# edition4-mainpart-3.net
KiCad netlist of a schematic drawn in EAGLE
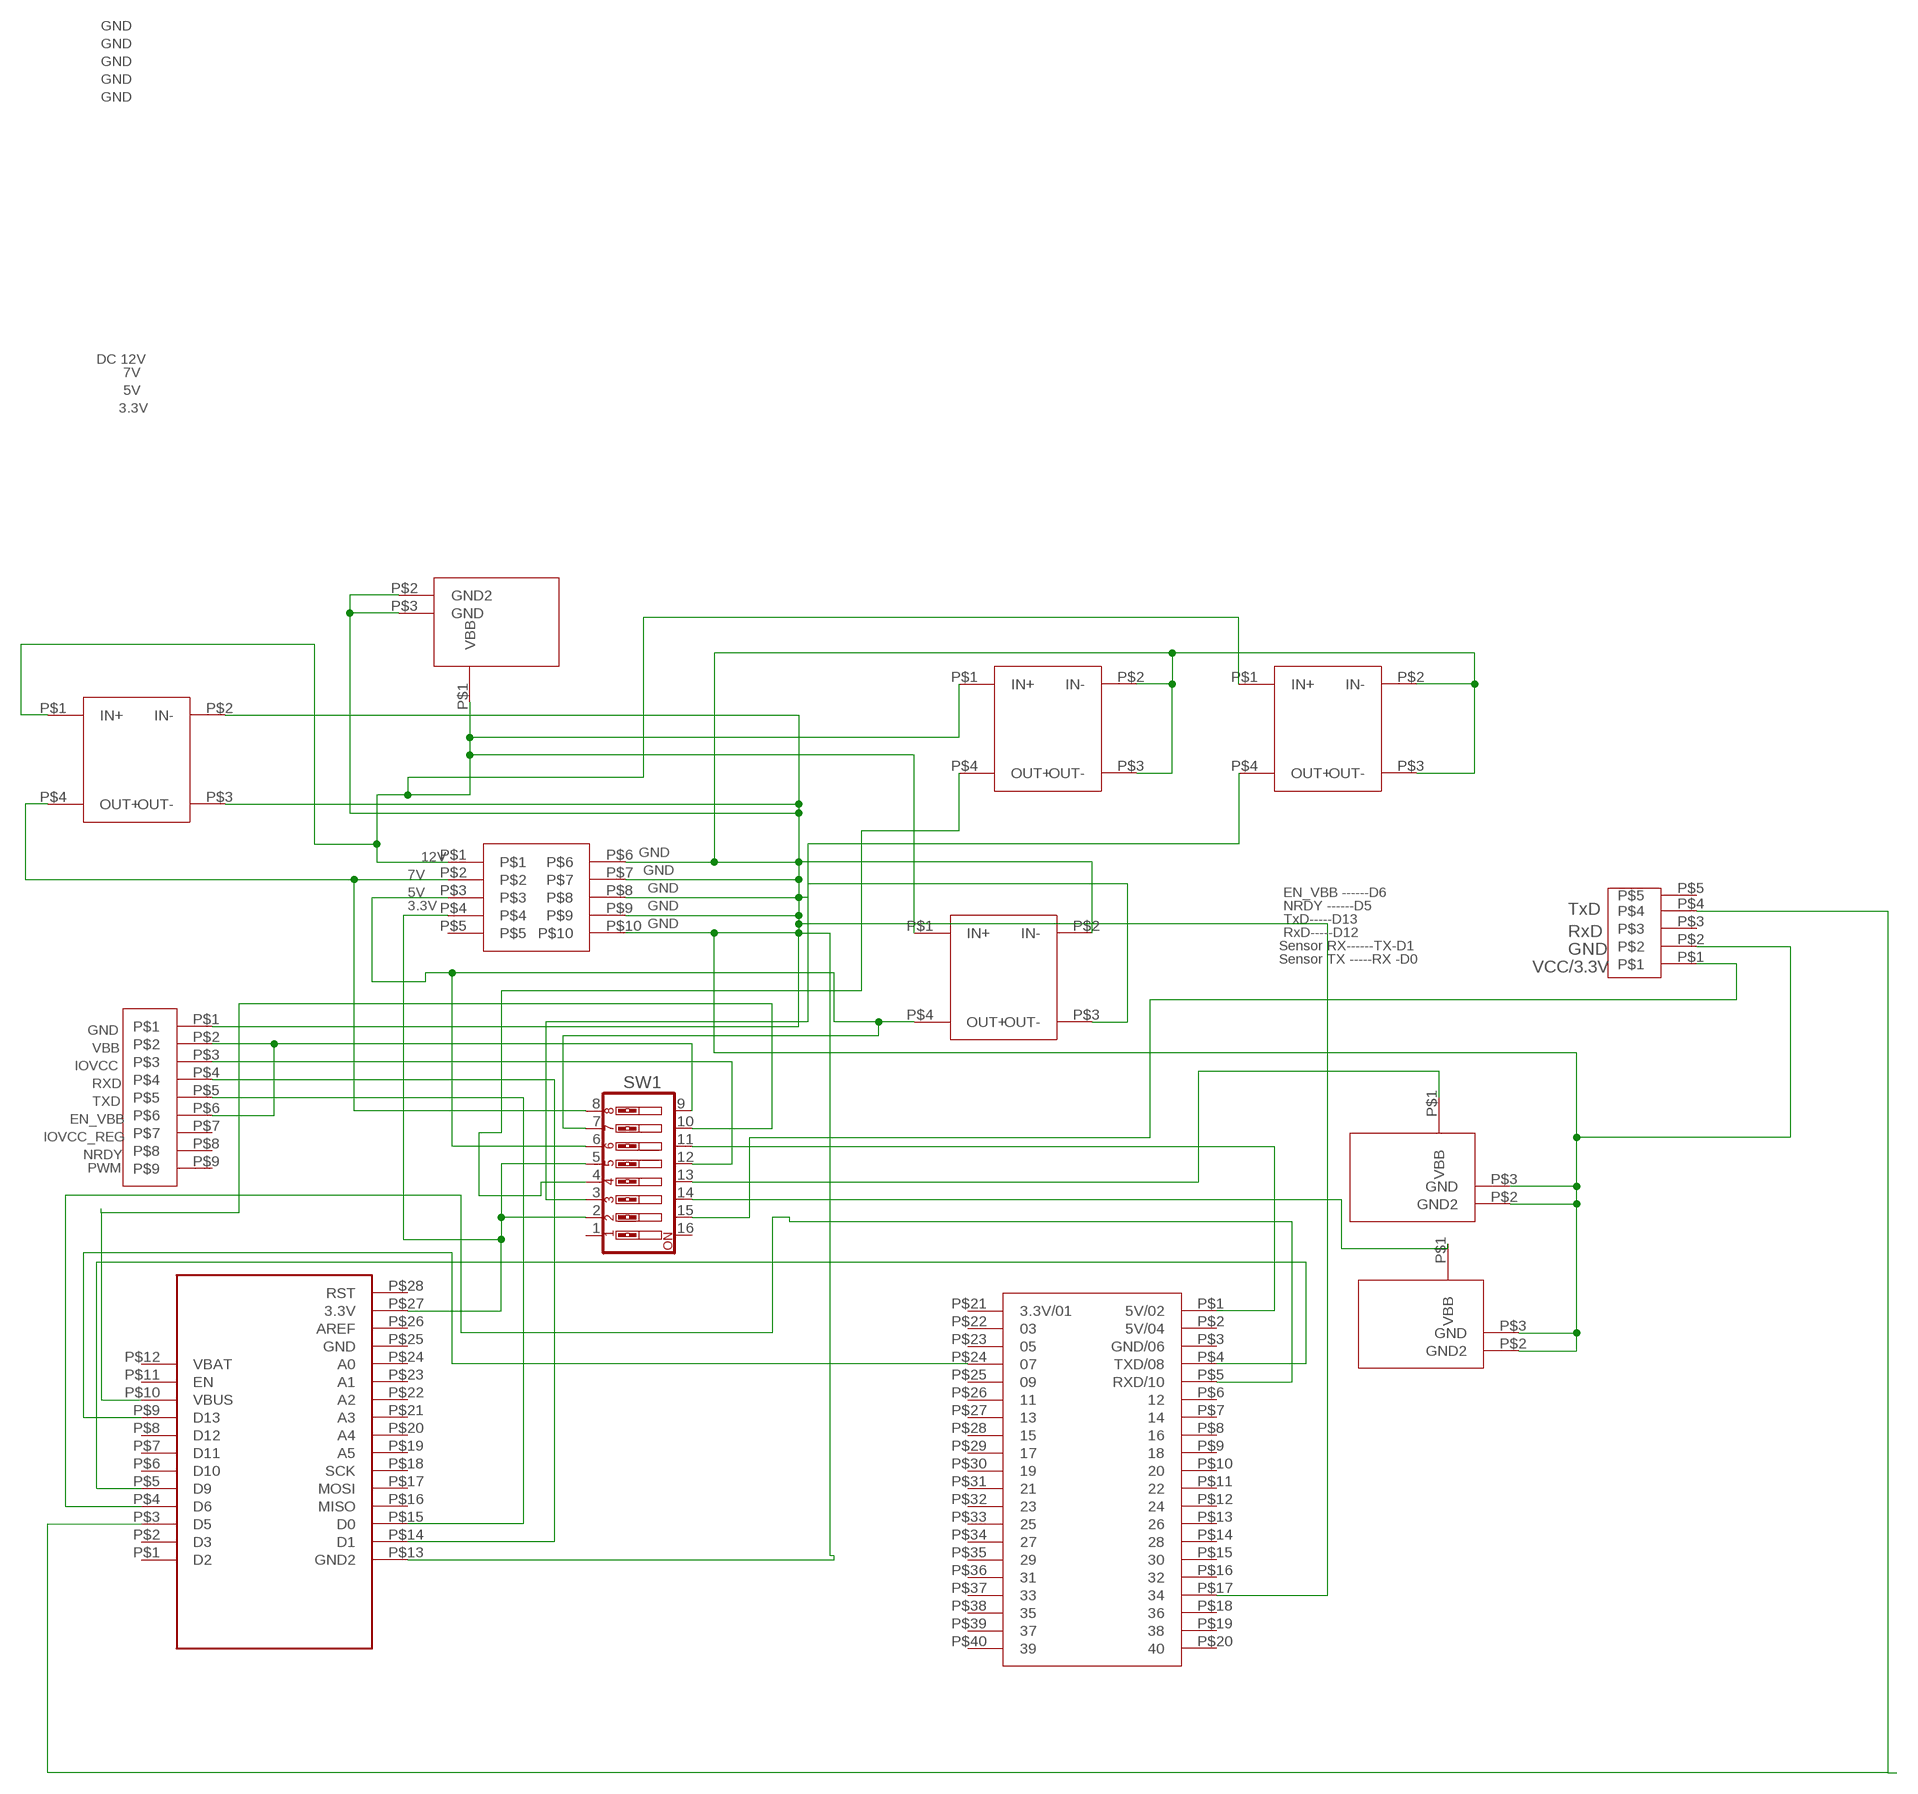
[diagram p0: schematic, sheet 1]

(export (version "E")
  (design (tool "Eeschema 10.0.6"))
  (components
    (comp (ref "SW1")
      (value "SW_DIP-8")
      (footprint "eagle-import:EDG-08")
      (libsource (lib "eagle-import") (part "SW_DIP-8"))
    )
    (comp (ref "U$1")
      (value "MH-MINI-360")
      (footprint "eagle-import:MH-MINI-360")
      (libsource (lib "eagle-import") (part "MH-MINI-360"))
    )
    (comp (ref "U$2")
      (value "MH-MINI-360")
      (footprint "eagle-import:MH-MINI-360")
      (libsource (lib "eagle-import") (part "MH-MINI-360"))
    )
    (comp (ref "U$3")
      (value "POWER")
      (footprint "eagle-import:POWERIN")
      (libsource (lib "eagle-import") (part "POWER"))
    )
    (comp (ref "U$4")
      (value "POWER")
      (footprint "eagle-import:POWERIN")
      (libsource (lib "eagle-import") (part "POWER"))
    )
    (comp (ref "U$5")
      (value "POWER")
      (footprint "eagle-import:POWERIN")
      (libsource (lib "eagle-import") (part "POWER"))
    )
    (comp (ref "U$6")
      (value "MH-MINI-360")
      (footprint "eagle-import:MH-MINI-360")
      (libsource (lib "eagle-import") (part "MH-MINI-360"))
    )
    (comp (ref "U$7")
      (value "MH-MINI-360")
      (footprint "eagle-import:MH-MINI-360")
      (libsource (lib "eagle-import") (part "MH-MINI-360"))
    )
    (comp (ref "U$8")
      (value "PIN")
      (footprint "eagle-import:PIN")
      (libsource (lib "eagle-import") (part "PIN"))
    )
    (comp (ref "U$10")
      (value "FEATHER")
      (footprint "eagle-import:FEATHER")
      (libsource (lib "eagle-import") (part "FEATHER"))
    )
    (comp (ref "U$11")
      (value "RASPBERRYPI")
      (footprint "eagle-import:RASPBERRYPI")
      (libsource (lib "eagle-import") (part "RASPBERRYPI"))
    )
    (comp (ref "U$14")
      (value "2X5FEET")
      (footprint "eagle-import:2X5FEET")
      (libsource (lib "eagle-import") (part "2X5FEET"))
    )
    (comp (ref "U$15")
      (value "9FEETPIN")
      (footprint "eagle-import:9FEETPIN")
      (libsource (lib "eagle-import") (part "9FEETPIN"))
    )
  )
  (nets
    (net (code "1") (name "Net-(SW1-Pad9)") (class "Default")
      (node (ref "SW1") (pin "9") (pinfunction "9_9") (pintype "passive"))
      (node (ref "U$15") (pin "P$2") (pinfunction "P$2_P$2") (pintype "bidirectional"))
      (node (ref "U$15") (pin "P$6") (pinfunction "P$6_P$6") (pintype "bidirectional"))
    )
    (net (code "2") (name "Net-(SW1-Pad12)") (class "Default")
      (node (ref "SW1") (pin "12") (pinfunction "12_12") (pintype "passive"))
      (node (ref "U$15") (pin "P$3") (pinfunction "P$3_P$3") (pintype "bidirectional"))
    )
    (net (code "3") (name "Net-(SW1-Pad15)") (class "Default")
      (node (ref "SW1") (pin "15") (pinfunction "15_15") (pintype "passive"))
      (node (ref "U$8") (pin "P$1") (pinfunction "P$1_P$1") (pintype "bidirectional"))
    )
    (net (code "4") (name "Net-(U$1-IN+)") (class "Default")
      (node (ref "U$1") (pin "P$1") (pinfunction "IN+_P$1") (pintype "bidirectional"))
      (node (ref "U$14") (pin "P$1") (pinfunction "P$1_P$1") (pintype "bidirectional"))
      (node (ref "U$2") (pin "P$1") (pinfunction "IN+_P$1") (pintype "bidirectional"))
      (node (ref "U$3") (pin "P$1") (pinfunction "VBB_P$1") (pintype "bidirectional"))
      (node (ref "U$6") (pin "P$1") (pinfunction "IN+_P$1") (pintype "bidirectional"))
      (node (ref "U$7") (pin "P$1") (pinfunction "IN+_P$1") (pintype "bidirectional"))
    )
    (net (code "5") (name "Net-(U$1-IN-)") (class "Default")
      (node (ref "U$1") (pin "P$2") (pinfunction "IN-_P$2") (pintype "bidirectional"))
      (node (ref "U$1") (pin "P$3") (pinfunction "OUT-_P$3") (pintype "bidirectional"))
      (node (ref "U$10") (pin "P$13") (pinfunction "GND2_P$13") (pintype "bidirectional"))
      (node (ref "U$11") (pin "P$17") (pinfunction "34_P$17") (pintype "bidirectional"))
      (node (ref "U$14") (pin "P$10") (pinfunction "P$10_P$10") (pintype "bidirectional"))
      (node (ref "U$14") (pin "P$6") (pinfunction "P$6_P$6") (pintype "bidirectional"))
      (node (ref "U$14") (pin "P$7") (pinfunction "P$7_P$7") (pintype "bidirectional"))
      (node (ref "U$14") (pin "P$8") (pinfunction "P$8_P$8") (pintype "bidirectional"))
      (node (ref "U$14") (pin "P$9") (pinfunction "P$9_P$9") (pintype "bidirectional"))
      (node (ref "U$15") (pin "P$1") (pinfunction "P$1_P$1") (pintype "bidirectional"))
      (node (ref "U$2") (pin "P$2") (pinfunction "IN-_P$2") (pintype "bidirectional"))
      (node (ref "U$2") (pin "P$3") (pinfunction "OUT-_P$3") (pintype "bidirectional"))
      (node (ref "U$3") (pin "P$2") (pinfunction "GND2_P$2") (pintype "bidirectional"))
      (node (ref "U$3") (pin "P$3") (pinfunction "GND_P$3") (pintype "bidirectional"))
      (node (ref "U$4") (pin "P$2") (pinfunction "GND2_P$2") (pintype "bidirectional"))
      (node (ref "U$4") (pin "P$3") (pinfunction "GND_P$3") (pintype "bidirectional"))
      (node (ref "U$5") (pin "P$2") (pinfunction "GND2_P$2") (pintype "bidirectional"))
      (node (ref "U$5") (pin "P$3") (pinfunction "GND_P$3") (pintype "bidirectional"))
      (node (ref "U$6") (pin "P$2") (pinfunction "IN-_P$2") (pintype "bidirectional"))
      (node (ref "U$6") (pin "P$3") (pinfunction "OUT-_P$3") (pintype "bidirectional"))
      (node (ref "U$7") (pin "P$2") (pinfunction "IN-_P$2") (pintype "bidirectional"))
      (node (ref "U$7") (pin "P$3") (pinfunction "OUT-_P$3") (pintype "bidirectional"))
      (node (ref "U$8") (pin "P$2") (pinfunction "P$2_P$2") (pintype "bidirectional"))
    )
    (net (code "6") (name "Net-(U$1-OUT+)") (class "Default")
      (node (ref "SW1") (pin "4") (pinfunction "4_4") (pintype "passive"))
      (node (ref "U$1") (pin "P$4") (pinfunction "OUT+_P$4") (pintype "bidirectional"))
    )
    (net (code "7") (name "Net-(U$2-OUT+)") (class "Default")
      (node (ref "SW1") (pin "6") (pinfunction "6_6") (pintype "passive"))
      (node (ref "SW1") (pin "7") (pinfunction "7_7") (pintype "passive"))
      (node (ref "U$14") (pin "P$3") (pinfunction "P$3_P$3") (pintype "bidirectional"))
      (node (ref "U$2") (pin "P$4") (pinfunction "OUT+_P$4") (pintype "bidirectional"))
    )
    (net (code "8") (name "Net-(U$4-VBB)") (class "Default")
      (node (ref "SW1") (pin "14") (pinfunction "14_14") (pintype "passive"))
      (node (ref "U$4") (pin "P$1") (pinfunction "VBB_P$1") (pintype "bidirectional"))
    )
    (net (code "9") (name "Net-(U$5-VBB)") (class "Default")
      (node (ref "SW1") (pin "13") (pinfunction "13_13") (pintype "passive"))
      (node (ref "U$5") (pin "P$1") (pinfunction "VBB_P$1") (pintype "bidirectional"))
    )
    (net (code "10") (name "Net-(U$6-OUT+)") (class "Default")
      (node (ref "SW1") (pin "8") (pinfunction "8_8") (pintype "passive"))
      (node (ref "U$14") (pin "P$2") (pinfunction "P$2_P$2") (pintype "bidirectional"))
      (node (ref "U$6") (pin "P$4") (pinfunction "OUT+_P$4") (pintype "bidirectional"))
    )
    (net (code "11") (name "Net-(U$7-OUT+)") (class "Default")
      (node (ref "SW1") (pin "3") (pinfunction "3_3") (pintype "passive"))
      (node (ref "U$7") (pin "P$4") (pinfunction "OUT+_P$4") (pintype "bidirectional"))
    )
    (net (code "12") (name "Net-(U$10-3.3V)") (class "Default")
      (node (ref "SW1") (pin "2") (pinfunction "2_2") (pintype "passive"))
      (node (ref "SW1") (pin "5") (pinfunction "5_5") (pintype "passive"))
      (node (ref "U$10") (pin "P$27") (pinfunction "3.3V_P$27") (pintype "bidirectional"))
      (node (ref "U$14") (pin "P$4") (pinfunction "P$4_P$4") (pintype "bidirectional"))
    )
    (net (code "13") (name "Net-(U$10-D0)") (class "Default")
      (node (ref "U$10") (pin "P$15") (pinfunction "D0_P$15") (pintype "bidirectional"))
      (node (ref "U$15") (pin "P$5") (pinfunction "P$5_P$5") (pintype "bidirectional"))
    )
    (net (code "14") (name "Net-(U$10-D1)") (class "Default")
      (node (ref "U$10") (pin "P$14") (pinfunction "D1_P$14") (pintype "bidirectional"))
      (node (ref "U$15") (pin "P$4") (pinfunction "P$4_P$4") (pintype "bidirectional"))
    )
    (net (code "15") (name "Net-(U$10-D5)") (class "Default")
      (node (ref "U$10") (pin "P$3") (pinfunction "D5_P$3") (pintype "bidirectional"))
      (node (ref "U$8") (pin "P$4") (pinfunction "P$4_P$4") (pintype "bidirectional"))
    )
    (net (code "16") (name "Net-(U$10-D6)") (class "Default")
      (node (ref "U$10") (pin "P$4") (pinfunction "D6_P$4") (pintype "bidirectional"))
      (node (ref "U$11") (pin "P$5") (pinfunction "RXD/10_P$5") (pintype "bidirectional"))
    )
    (net (code "17") (name "Net-(U$10-D9)") (class "Default")
      (node (ref "U$10") (pin "P$5") (pinfunction "D9_P$5") (pintype "bidirectional"))
      (node (ref "U$11") (pin "P$4") (pinfunction "TXD/08_P$4") (pintype "bidirectional"))
    )
    (net (code "18") (name "Net-(U$10-D13)") (class "Default")
      (node (ref "U$10") (pin "P$9") (pinfunction "D13_P$9") (pintype "bidirectional"))
      (node (ref "U$11") (pin "P$24") (pinfunction "07_P$24") (pintype "bidirectional"))
    )
    (net (code "19") (name "Net-(U$10-VBUS)") (class "Default")
      (node (ref "SW1") (pin "10") (pinfunction "10_10") (pintype "passive"))
      (node (ref "U$10") (pin "P$10") (pinfunction "VBUS_P$10") (pintype "bidirectional"))
    )
    (net (code "20") (name "Net-(U$11-5V{slash}02)") (class "Default")
      (node (ref "SW1") (pin "11") (pinfunction "11_11") (pintype "passive"))
      (node (ref "U$11") (pin "P$1") (pinfunction "5V/02_P$1") (pintype "bidirectional"))
    )
    (net (code "21") (name "unconnected-(SW1-Pad1)") (class "Default")
      (node (ref "SW1") (pin "1") (pinfunction "1_1") (pintype "passive"))
    )
    (net (code "22") (name "unconnected-(SW1-Pad16)") (class "Default")
      (node (ref "SW1") (pin "16") (pinfunction "16_16") (pintype "passive"))
    )
    (net (code "23") (name "unconnected-(U$8-PadP$3)") (class "Default")
      (node (ref "U$8") (pin "P$3") (pinfunction "P$3_P$3") (pintype "bidirectional"))
    )
    (net (code "24") (name "unconnected-(U$8-PadP$5)") (class "Default")
      (node (ref "U$8") (pin "P$5") (pinfunction "P$5_P$5") (pintype "bidirectional"))
    )
    (net (code "25") (name "unconnected-(U$10-A0-PadP$24)") (class "Default")
      (node (ref "U$10") (pin "P$24") (pinfunction "A0_P$24") (pintype "bidirectional"))
    )
    (net (code "26") (name "unconnected-(U$10-A1-PadP$23)") (class "Default")
      (node (ref "U$10") (pin "P$23") (pinfunction "A1_P$23") (pintype "bidirectional"))
    )
    (net (code "27") (name "unconnected-(U$10-A2-PadP$22)") (class "Default")
      (node (ref "U$10") (pin "P$22") (pinfunction "A2_P$22") (pintype "bidirectional"))
    )
    (net (code "28") (name "unconnected-(U$10-A3-PadP$21)") (class "Default")
      (node (ref "U$10") (pin "P$21") (pinfunction "A3_P$21") (pintype "bidirectional"))
    )
    (net (code "29") (name "unconnected-(U$10-A4-PadP$20)") (class "Default")
      (node (ref "U$10") (pin "P$20") (pinfunction "A4_P$20") (pintype "bidirectional"))
    )
    (net (code "30") (name "unconnected-(U$10-A5-PadP$19)") (class "Default")
      (node (ref "U$10") (pin "P$19") (pinfunction "A5_P$19") (pintype "bidirectional"))
    )
    (net (code "31") (name "unconnected-(U$10-AREF-PadP$26)") (class "Default")
      (node (ref "U$10") (pin "P$26") (pinfunction "AREF_P$26") (pintype "bidirectional"))
    )
    (net (code "32") (name "unconnected-(U$10-D2-PadP$1)") (class "Default")
      (node (ref "U$10") (pin "P$1") (pinfunction "D2_P$1") (pintype "bidirectional"))
    )
    (net (code "33") (name "unconnected-(U$10-D3-PadP$2)") (class "Default")
      (node (ref "U$10") (pin "P$2") (pinfunction "D3_P$2") (pintype "bidirectional"))
    )
    (net (code "34") (name "unconnected-(U$10-D10-PadP$6)") (class "Default")
      (node (ref "U$10") (pin "P$6") (pinfunction "D10_P$6") (pintype "bidirectional"))
    )
    (net (code "35") (name "unconnected-(U$10-D11-PadP$7)") (class "Default")
      (node (ref "U$10") (pin "P$7") (pinfunction "D11_P$7") (pintype "bidirectional"))
    )
    (net (code "36") (name "unconnected-(U$10-D12-PadP$8)") (class "Default")
      (node (ref "U$10") (pin "P$8") (pinfunction "D12_P$8") (pintype "bidirectional"))
    )
    (net (code "37") (name "unconnected-(U$10-EN-PadP$11)") (class "Default")
      (node (ref "U$10") (pin "P$11") (pinfunction "EN_P$11") (pintype "bidirectional"))
    )
    (net (code "38") (name "unconnected-(U$10-GND-PadP$25)") (class "Default")
      (node (ref "U$10") (pin "P$25") (pinfunction "GND_P$25") (pintype "bidirectional"))
    )
    (net (code "39") (name "unconnected-(U$10-MISO-PadP$16)") (class "Default")
      (node (ref "U$10") (pin "P$16") (pinfunction "MISO_P$16") (pintype "bidirectional"))
    )
    (net (code "40") (name "unconnected-(U$10-MOSI-PadP$17)") (class "Default")
      (node (ref "U$10") (pin "P$17") (pinfunction "MOSI_P$17") (pintype "bidirectional"))
    )
    (net (code "41") (name "unconnected-(U$10-RST-PadP$28)") (class "Default")
      (node (ref "U$10") (pin "P$28") (pinfunction "RST_P$28") (pintype "bidirectional"))
    )
    (net (code "42") (name "unconnected-(U$10-SCK-PadP$18)") (class "Default")
      (node (ref "U$10") (pin "P$18") (pinfunction "SCK_P$18") (pintype "bidirectional"))
    )
    (net (code "43") (name "unconnected-(U$10-VBAT-PadP$12)") (class "Default")
      (node (ref "U$10") (pin "P$12") (pinfunction "VBAT_P$12") (pintype "bidirectional"))
    )
    (net (code "44") (name "unconnected-(U$11-03-PadP$22)") (class "Default")
      (node (ref "U$11") (pin "P$22") (pinfunction "03_P$22") (pintype "bidirectional"))
    )
    (net (code "45") (name "unconnected-(U$11-3.3V{slash}01-PadP$21)") (class "Default")
      (node (ref "U$11") (pin "P$21") (pinfunction "3.3V/01_P$21") (pintype "bidirectional"))
    )
    (net (code "46") (name "unconnected-(U$11-05-PadP$23)") (class "Default")
      (node (ref "U$11") (pin "P$23") (pinfunction "05_P$23") (pintype "bidirectional"))
    )
    (net (code "47") (name "unconnected-(U$11-5V{slash}04-PadP$2)") (class "Default")
      (node (ref "U$11") (pin "P$2") (pinfunction "5V/04_P$2") (pintype "bidirectional"))
    )
    (net (code "48") (name "unconnected-(U$11-09-PadP$25)") (class "Default")
      (node (ref "U$11") (pin "P$25") (pinfunction "09_P$25") (pintype "bidirectional"))
    )
    (net (code "49") (name "unconnected-(U$11-11-PadP$26)") (class "Default")
      (node (ref "U$11") (pin "P$26") (pinfunction "11_P$26") (pintype "bidirectional"))
    )
    (net (code "50") (name "unconnected-(U$11-12-PadP$6)") (class "Default")
      (node (ref "U$11") (pin "P$6") (pinfunction "12_P$6") (pintype "bidirectional"))
    )
    (net (code "51") (name "unconnected-(U$11-13-PadP$27)") (class "Default")
      (node (ref "U$11") (pin "P$27") (pinfunction "13_P$27") (pintype "bidirectional"))
    )
    (net (code "52") (name "unconnected-(U$11-14-PadP$7)") (class "Default")
      (node (ref "U$11") (pin "P$7") (pinfunction "14_P$7") (pintype "bidirectional"))
    )
    (net (code "53") (name "unconnected-(U$11-15-PadP$28)") (class "Default")
      (node (ref "U$11") (pin "P$28") (pinfunction "15_P$28") (pintype "bidirectional"))
    )
    (net (code "54") (name "unconnected-(U$11-16-PadP$8)") (class "Default")
      (node (ref "U$11") (pin "P$8") (pinfunction "16_P$8") (pintype "bidirectional"))
    )
    (net (code "55") (name "unconnected-(U$11-17-PadP$29)") (class "Default")
      (node (ref "U$11") (pin "P$29") (pinfunction "17_P$29") (pintype "bidirectional"))
    )
    (net (code "56") (name "unconnected-(U$11-18-PadP$9)") (class "Default")
      (node (ref "U$11") (pin "P$9") (pinfunction "18_P$9") (pintype "bidirectional"))
    )
    (net (code "57") (name "unconnected-(U$11-19-PadP$30)") (class "Default")
      (node (ref "U$11") (pin "P$30") (pinfunction "19_P$30") (pintype "bidirectional"))
    )
    (net (code "58") (name "unconnected-(U$11-20-PadP$10)") (class "Default")
      (node (ref "U$11") (pin "P$10") (pinfunction "20_P$10") (pintype "bidirectional"))
    )
    (net (code "59") (name "unconnected-(U$11-21-PadP$31)") (class "Default")
      (node (ref "U$11") (pin "P$31") (pinfunction "21_P$31") (pintype "bidirectional"))
    )
    (net (code "60") (name "unconnected-(U$11-22-PadP$11)") (class "Default")
      (node (ref "U$11") (pin "P$11") (pinfunction "22_P$11") (pintype "bidirectional"))
    )
    (net (code "61") (name "unconnected-(U$11-23-PadP$32)") (class "Default")
      (node (ref "U$11") (pin "P$32") (pinfunction "23_P$32") (pintype "bidirectional"))
    )
    (net (code "62") (name "unconnected-(U$11-24-PadP$12)") (class "Default")
      (node (ref "U$11") (pin "P$12") (pinfunction "24_P$12") (pintype "bidirectional"))
    )
    (net (code "63") (name "unconnected-(U$11-25-PadP$33)") (class "Default")
      (node (ref "U$11") (pin "P$33") (pinfunction "25_P$33") (pintype "bidirectional"))
    )
    (net (code "64") (name "unconnected-(U$11-26-PadP$13)") (class "Default")
      (node (ref "U$11") (pin "P$13") (pinfunction "26_P$13") (pintype "bidirectional"))
    )
    (net (code "65") (name "unconnected-(U$11-27-PadP$34)") (class "Default")
      (node (ref "U$11") (pin "P$34") (pinfunction "27_P$34") (pintype "bidirectional"))
    )
    (net (code "66") (name "unconnected-(U$11-28-PadP$14)") (class "Default")
      (node (ref "U$11") (pin "P$14") (pinfunction "28_P$14") (pintype "bidirectional"))
    )
    (net (code "67") (name "unconnected-(U$11-29-PadP$35)") (class "Default")
      (node (ref "U$11") (pin "P$35") (pinfunction "29_P$35") (pintype "bidirectional"))
    )
    (net (code "68") (name "unconnected-(U$11-30-PadP$15)") (class "Default")
      (node (ref "U$11") (pin "P$15") (pinfunction "30_P$15") (pintype "bidirectional"))
    )
    (net (code "69") (name "unconnected-(U$11-31-PadP$36)") (class "Default")
      (node (ref "U$11") (pin "P$36") (pinfunction "31_P$36") (pintype "bidirectional"))
    )
    (net (code "70") (name "unconnected-(U$11-32-PadP$16)") (class "Default")
      (node (ref "U$11") (pin "P$16") (pinfunction "32_P$16") (pintype "bidirectional"))
    )
    (net (code "71") (name "unconnected-(U$11-33-PadP$37)") (class "Default")
      (node (ref "U$11") (pin "P$37") (pinfunction "33_P$37") (pintype "bidirectional"))
    )
    (net (code "72") (name "unconnected-(U$11-35-PadP$38)") (class "Default")
      (node (ref "U$11") (pin "P$38") (pinfunction "35_P$38") (pintype "bidirectional"))
    )
    (net (code "73") (name "unconnected-(U$11-36-PadP$18)") (class "Default")
      (node (ref "U$11") (pin "P$18") (pinfunction "36_P$18") (pintype "bidirectional"))
    )
    (net (code "74") (name "unconnected-(U$11-37-PadP$39)") (class "Default")
      (node (ref "U$11") (pin "P$39") (pinfunction "37_P$39") (pintype "bidirectional"))
    )
    (net (code "75") (name "unconnected-(U$11-38-PadP$19)") (class "Default")
      (node (ref "U$11") (pin "P$19") (pinfunction "38_P$19") (pintype "bidirectional"))
    )
    (net (code "76") (name "unconnected-(U$11-39-PadP$40)") (class "Default")
      (node (ref "U$11") (pin "P$40") (pinfunction "39_P$40") (pintype "bidirectional"))
    )
    (net (code "77") (name "unconnected-(U$11-40-PadP$20)") (class "Default")
      (node (ref "U$11") (pin "P$20") (pinfunction "40_P$20") (pintype "bidirectional"))
    )
    (net (code "78") (name "unconnected-(U$11-GND{slash}06-PadP$3)") (class "Default")
      (node (ref "U$11") (pin "P$3") (pinfunction "GND/06_P$3") (pintype "bidirectional"))
    )
    (net (code "79") (name "unconnected-(U$14-PadP$5)") (class "Default")
      (node (ref "U$14") (pin "P$5") (pinfunction "P$5_P$5") (pintype "bidirectional"))
    )
    (net (code "80") (name "unconnected-(U$15-PadP$7)") (class "Default")
      (node (ref "U$15") (pin "P$7") (pinfunction "P$7_P$7") (pintype "bidirectional"))
    )
    (net (code "81") (name "unconnected-(U$15-PadP$8)") (class "Default")
      (node (ref "U$15") (pin "P$8") (pinfunction "P$8_P$8") (pintype "bidirectional"))
    )
    (net (code "82") (name "unconnected-(U$15-PadP$9)") (class "Default")
      (node (ref "U$15") (pin "P$9") (pinfunction "P$9_P$9") (pintype "bidirectional"))
    )
  )
)
